# Power_and_can.net
KiCad netlist of a schematic drawn in Altium Designer
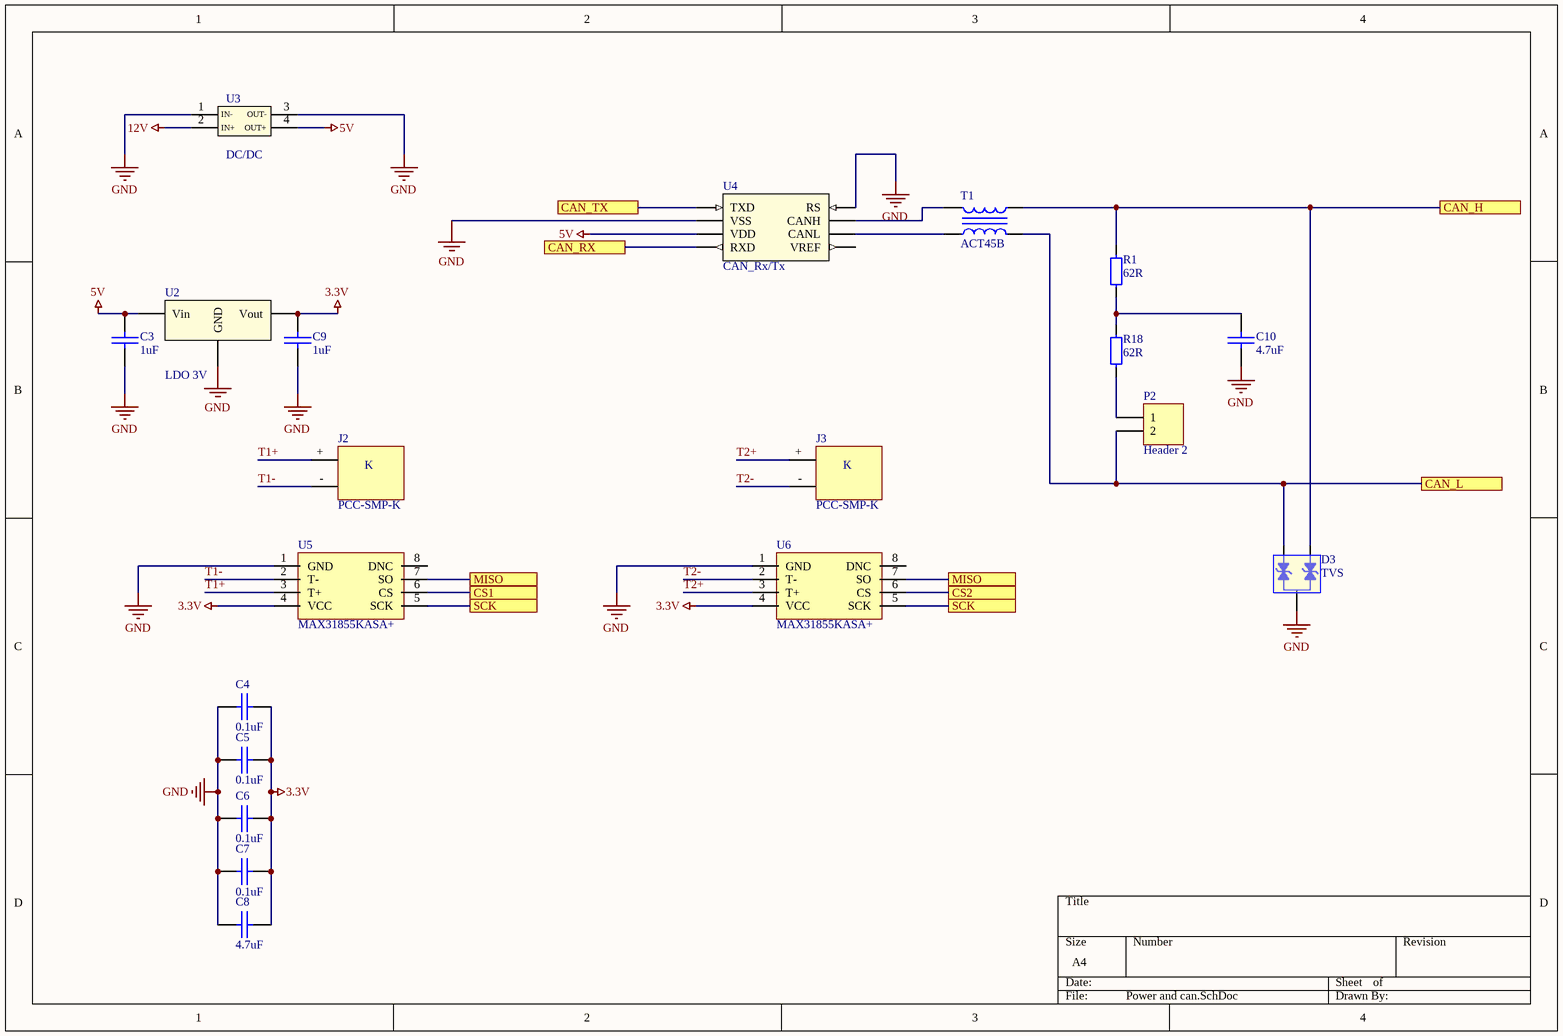
[diagram p0: Power and can.SchDoc]

(export (version "E")
  (design (tool "Eeschema 10.0.6"))
  (components
    (comp (ref "C3")
      (value "1uF")
      (footprint "0805 Capicator")
      (description "1uF X7R 10% 16V 0805")
      (fields
        (field (name "MANUFACTURER") "Murata Manufacturing")
        (field (name "PART NUMBER") "GRM21BR71C105KA01K")
      )
      (libsource (lib "BRT_Components") (part "Cap 1uF (0805)"))
    )
    (comp (ref "C4")
      (value "0.1uF")
      (footprint "0805 Capicator")
      (description "0.1uF X7R 50V 10% 0805")
      (fields
        (field (name "MANUFACTURER") "Murata Manufacturing")
        (field (name "PART NUMBER") "GRM21BR71H104K")
      )
      (libsource (lib "BRT_Components") (part "Cap 0.1uF (0805)"))
    )
    (comp (ref "C5")
      (value "0.1uF")
      (footprint "0805 Capicator")
      (description "0.1uF X7R 50V 10% 0805")
      (fields
        (field (name "MANUFACTURER") "Murata Manufacturing")
        (field (name "PART NUMBER") "GRM21BR71H104K")
      )
      (libsource (lib "BRT_Components") (part "Cap 0.1uF (0805)"))
    )
    (comp (ref "C6")
      (value "0.1uF")
      (footprint "0805 Capicator")
      (description "0.1uF X7R 50V 10% 0805")
      (fields
        (field (name "MANUFACTURER") "Murata Manufacturing")
        (field (name "PART NUMBER") "GRM21BR71H104K")
      )
      (libsource (lib "BRT_Components") (part "Cap 0.1uF (0805)"))
    )
    (comp (ref "C7")
      (value "0.1uF")
      (footprint "0805 Capicator")
      (description "0.1uF X7R 50V 10% 0805")
      (fields
        (field (name "MANUFACTURER") "Murata Manufacturing")
        (field (name "PART NUMBER") "GRM21BR71H104K")
      )
      (libsource (lib "BRT_Components") (part "Cap 0.1uF (0805)"))
    )
    (comp (ref "C8")
      (value "4.7uF")
      (footprint "0805 Capicator")
      (description "4.7uF X5R 10% 25V 0805")
      (fields
        (field (name "MANUFACTURER") "Murata Manufacturing")
        (field (name "PART NUMBER") "GRM21BR61E475KA12L")
      )
      (libsource (lib "BRT_Components") (part "Cap 4.7uF (0805)"))
    )
    (comp (ref "C9")
      (value "1uF")
      (footprint "0805 Capicator")
      (description "1uF X7R 10% 16V 0805")
      (fields
        (field (name "MANUFACTURER") "Murata Manufacturing")
        (field (name "PART NUMBER") "GRM21BR71C105KA01K")
      )
      (libsource (lib "BRT_Components") (part "Cap 1uF (0805)"))
    )
    (comp (ref "C10")
      (value "4.7uF")
      (footprint "0805 Capicator")
      (description "4.7uF X5R 10% 25V 0805")
      (fields
        (field (name "MANUFACTURER") "Murata Manufacturing")
        (field (name "PART NUMBER") "GRM21BR61E475KA12L")
      )
      (libsource (lib "BRT_Components") (part "Cap 4.7uF (0805)"))
    )
    (comp (ref "D3")
      (value "TVS")
      (footprint "SOT-23")
      (fields (field (name "PART NUMBER") "SM24CANB-02HTG") (field (name "MANUFACTURER") "Littelfuse"))
      (libsource (lib "BRT_Components") (part "TVS Diode Arrays"))
    )
    (comp (ref "J2")
      (value "PCC-SMP-K")
      (footprint "thermocouple")
      (libsource (lib "thermocouple") (part "thermocoupleconnector"))
    )
    (comp (ref "J3")
      (value "PCC-SMP-K")
      (footprint "thermocouple")
      (libsource (lib "thermocouple") (part "thermocoupleconnector"))
    )
    (comp (ref "P2")
      (value "Header 2")
      (footprint "HDR1X2")
      (description "Header, 2-Pin")
      (fields (field (name "PUBLISHER") "Altium Limited"))
      (libsource (lib "Miscellaneous Connectors") (part "Header 2"))
    )
    (comp (ref "R1")
      (value "62R")
      (footprint "0805 Resistor")
      (description "0.125W 0805 62R, 1%")
      (fields (field (name "PART NUMBER") "RC0805FR-0762RL") (field (name "MANUFACTURER") "Taiwan"))
      (libsource (lib "BRT_Components") (part "Res 62R (0805)"))
    )
    (comp (ref "R18")
      (value "62R")
      (footprint "0805 Resistor")
      (description "0.125W 0805 62R, 1%")
      (fields (field (name "PART NUMBER") "RC0805FR-0762RL") (field (name "MANUFACTURER") "Taiwan"))
      (libsource (lib "BRT_Components") (part "Res 62R (0805)"))
    )
    (comp (ref "T1")
      (value "ACT45B")
      (footprint "ACT45B")
      (description "Common mode filters\r\nAutomotive signal line (for power train/safety)")
      (fields
        (field (name "MANUFACTURER") "EMC Components")
        (field (name "PART NUMBER") "ACT45B-510-2P-TL003")
      )
      (libsource (lib "BRT_Components") (part "ACT45B"))
    )
    (comp (ref "U2")
      (value "LDO 3V")
      (footprint "SOT-23")
      (description "MCP1702 Low Dropout Voltage Regulator. The input operating range is specifiedfrom 2.7V to 13.2V")
      (fields (field (name "PART NUMBER") "MCP1702T-3002E/CB") (field (name "MANUFACTURER") "Microchip"))
      (libsource (lib "BRT_Components") (part "LDO 3V [MCP]"))
    )
    (comp (ref "U3")
      (value "DC/DC")
      (footprint "DC-DC")
      (description "DC/DC 5V with MP2307 Chip")
      (libsource (lib "BRT_Components") (part "DC/DC"))
    )
    (comp (ref "U4")
      (value "CAN_Rx/Tx")
      (footprint "SO-8")
      (fields (field (name "PART NUMBER") "MCP2551-I/SN") (field (name "MANUFACTURER") "Microchip"))
      (libsource (lib "BRT_Components") (part "CAN Transceiver [MCP2551]"))
    )
    (comp (ref "U5")
      (value "MAX31855KASA+")
      (footprint "SO-8")
      (libsource (lib "thermocouple") (part "MAX31855KASA+"))
    )
    (comp (ref "U6")
      (value "MAX31855KASA+")
      (footprint "SO-8")
      (libsource (lib "thermocouple") (part "MAX31855KASA+"))
    )
  )
  (nets
    (net (code "1") (name "/CAN_H") (class "Default")
      (node (ref "D3") (pin "1") (pinfunction "1_1") (pintype "passive"))
      (node (ref "R1") (pin "2") (pinfunction "2_2") (pintype "passive"))
      (node (ref "T1") (pin "4") (pinfunction "4_4") (pintype "passive"))
    )
    (net (code "2") (name "/CAN_L") (class "Default")
      (node (ref "D3") (pin "2") (pinfunction "2_2") (pintype "passive"))
      (node (ref "P2") (pin "2") (pinfunction "2_2") (pintype "passive"))
      (node (ref "T1") (pin "3") (pinfunction "3_3") (pintype "passive"))
    )
    (net (code "3") (name "/CAN_RX") (class "Default")
      (node (ref "U4") (pin "4") (pinfunction "RXD_4") (pintype "output"))
    )
    (net (code "4") (name "/CAN_TX") (class "Default")
      (node (ref "U4") (pin "1") (pinfunction "TXD_1") (pintype "input"))
    )
    (net (code "5") (name "/CS1") (class "Default")
      (node (ref "U5") (pin "6") (pinfunction "CS_6") (pintype "passive"))
    )
    (net (code "6") (name "/CS2") (class "Default")
      (node (ref "U6") (pin "6") (pinfunction "CS_6") (pintype "passive"))
    )
    (net (code "7") (name "/MISO") (class "Default")
      (node (ref "U5") (pin "7") (pinfunction "SO_7") (pintype "passive"))
      (node (ref "U6") (pin "7") (pinfunction "SO_7") (pintype "passive"))
    )
    (net (code "8") (name "/SCK") (class "Default")
      (node (ref "U5") (pin "5") (pinfunction "SCK_5") (pintype "passive"))
      (node (ref "U6") (pin "5") (pinfunction "SCK_5") (pintype "passive"))
    )
    (net (code "9") (name "/T1+") (class "Default")
      (node (ref "J2") (pin "+") (pinfunction "31_+") (pintype "passive"))
      (node (ref "U5") (pin "3") (pinfunction "T+_3") (pintype "passive"))
    )
    (net (code "10") (name "/T1-") (class "Default")
      (node (ref "J2") (pin "-") (pinfunction "31_-") (pintype "passive"))
      (node (ref "U5") (pin "2") (pinfunction "T-_2") (pintype "passive"))
    )
    (net (code "11") (name "/T2+") (class "Default")
      (node (ref "J3") (pin "+") (pinfunction "31_+") (pintype "passive"))
      (node (ref "U6") (pin "3") (pinfunction "T+_3") (pintype "passive"))
    )
    (net (code "12") (name "/T2-") (class "Default")
      (node (ref "J3") (pin "-") (pinfunction "31_-") (pintype "passive"))
      (node (ref "U6") (pin "2") (pinfunction "T-_2") (pintype "passive"))
    )
    (net (code "13") (name "3.3V") (class "Default")
      (node (ref "C4") (pin "1") (pinfunction "1_1") (pintype "passive"))
      (node (ref "C5") (pin "1") (pinfunction "1_1") (pintype "passive"))
      (node (ref "C6") (pin "1") (pinfunction "1_1") (pintype "passive"))
      (node (ref "C7") (pin "1") (pinfunction "1_1") (pintype "passive"))
      (node (ref "C8") (pin "2") (pinfunction "2_2") (pintype "passive"))
      (node (ref "C9") (pin "1") (pinfunction "1_1") (pintype "passive"))
      (node (ref "U2") (pin "2") (pinfunction "Vout_2") (pintype "power_in"))
      (node (ref "U5") (pin "4") (pinfunction "VCC_4") (pintype "passive"))
      (node (ref "U6") (pin "4") (pinfunction "VCC_4") (pintype "passive"))
    )
    (net (code "14") (name "5V") (class "Default")
      (node (ref "C3") (pin "2") (pinfunction "2_2") (pintype "passive"))
      (node (ref "U2") (pin "3") (pinfunction "Vin_3") (pintype "power_in"))
      (node (ref "U3") (pin "4") (pinfunction "OUT+_4") (pintype "passive"))
      (node (ref "U4") (pin "3") (pinfunction "VDD_3") (pintype "power_in"))
    )
    (net (code "15") (name "12V") (class "Default")
      (node (ref "U3") (pin "2") (pinfunction "IN+_2") (pintype "passive"))
    )
    (net (code "16") (name "GND") (class "Default")
      (node (ref "C10") (pin "1") (pinfunction "1_1") (pintype "passive"))
      (node (ref "C3") (pin "1") (pinfunction "1_1") (pintype "passive"))
      (node (ref "C4") (pin "2") (pinfunction "2_2") (pintype "passive"))
      (node (ref "C5") (pin "2") (pinfunction "2_2") (pintype "passive"))
      (node (ref "C6") (pin "2") (pinfunction "2_2") (pintype "passive"))
      (node (ref "C7") (pin "2") (pinfunction "2_2") (pintype "passive"))
      (node (ref "C8") (pin "1") (pinfunction "1_1") (pintype "passive"))
      (node (ref "C9") (pin "2") (pinfunction "2_2") (pintype "passive"))
      (node (ref "D3") (pin "3") (pinfunction "3_3") (pintype "passive"))
      (node (ref "U2") (pin "1") (pinfunction "GND_1") (pintype "power_in"))
      (node (ref "U3") (pin "1") (pinfunction "IN-_1") (pintype "passive"))
      (node (ref "U3") (pin "3") (pinfunction "OUT-_3") (pintype "passive"))
      (node (ref "U4") (pin "2") (pinfunction "VSS_2") (pintype "power_in"))
      (node (ref "U4") (pin "8") (pinfunction "RS_8") (pintype "input"))
      (node (ref "U5") (pin "1") (pinfunction "GND_1") (pintype "passive"))
      (node (ref "U6") (pin "1") (pinfunction "GND_1") (pintype "passive"))
    )
    (net (code "17") (name "Net-(C10-Pad2)") (class "Default")
      (node (ref "C10") (pin "2") (pinfunction "2_2") (pintype "passive"))
      (node (ref "R1") (pin "1") (pinfunction "1_1") (pintype "passive"))
      (node (ref "R18") (pin "2") (pinfunction "2_2") (pintype "passive"))
    )
    (net (code "18") (name "Net-(P2-Pad1)") (class "Default")
      (node (ref "P2") (pin "1") (pinfunction "1_1") (pintype "passive"))
      (node (ref "R18") (pin "1") (pinfunction "1_1") (pintype "passive"))
    )
    (net (code "19") (name "Net-(U4-CANH)") (class "Default")
      (node (ref "T1") (pin "1") (pinfunction "1_1") (pintype "passive"))
      (node (ref "U4") (pin "7") (pinfunction "CANH_7") (pintype "open_collector"))
    )
    (net (code "20") (name "Net-(U4-CANL)") (class "Default")
      (node (ref "T1") (pin "2") (pinfunction "2_2") (pintype "passive"))
      (node (ref "U4") (pin "6") (pinfunction "CANL_6") (pintype "open_collector"))
    )
    (net (code "21") (name "unconnected-(U4-VREF-Pad5)") (class "Default")
      (node (ref "U4") (pin "5") (pinfunction "VREF_5") (pintype "output"))
    )
    (net (code "22") (name "unconnected-(U5-DNC-Pad8)") (class "Default")
      (node (ref "U5") (pin "8") (pinfunction "DNC_8") (pintype "passive"))
    )
    (net (code "23") (name "unconnected-(U6-DNC-Pad8)") (class "Default")
      (node (ref "U6") (pin "8") (pinfunction "DNC_8") (pintype "passive"))
    )
  )
)
